# Peripherals.net
KiCad netlist of a schematic drawn in Altium Designer
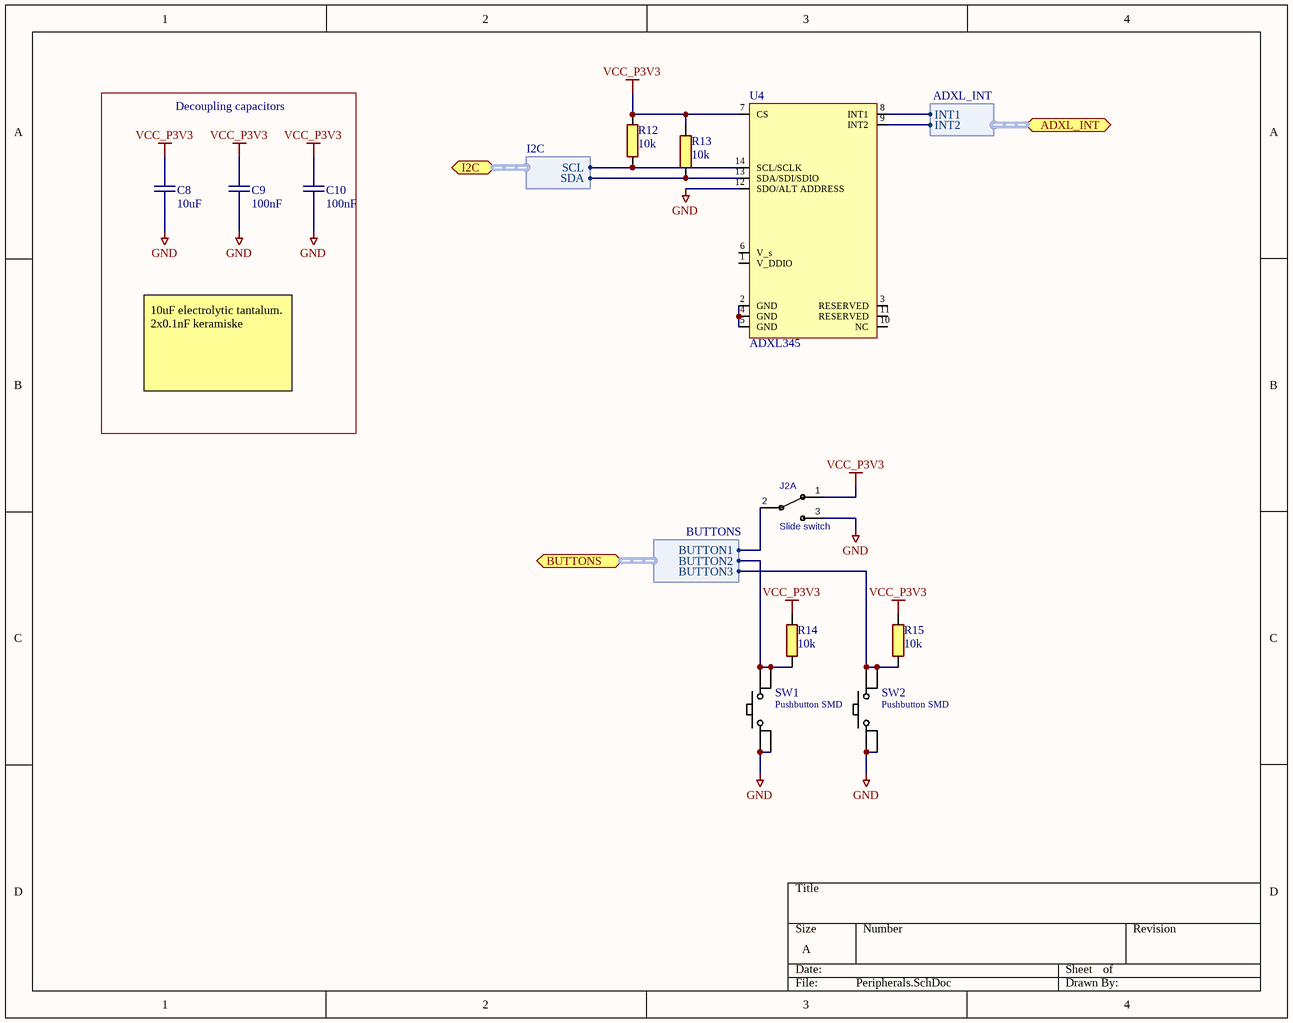
[diagram p0: Peripherals.SchDoc]

(export (version "E")
  (design (tool "Eeschema 10.0.6"))
  (components
    (comp (ref "C8")
      (value "10uF")
      (footprint "CAPC1206(3216)170_N")
      (description "X5R 50V 10%")
      (libsource (lib "OVLib") (part "CAP"))
    )
    (comp (ref "C9")
      (value "100nF")
      (footprint "CAPC0603(1608)55_N")
      (description "X7R 50V 5%")
      (libsource (lib "OVLib") (part "CAP"))
    )
    (comp (ref "C10")
      (value "100nF")
      (footprint "CAPC0603(1608)55_N")
      (description "X7R 50V 5%")
      (libsource (lib "OVLib") (part "CAP"))
    )
    (comp (ref "J2")
      (value "Slide switch")
      (footprint "OS202011MA0QS1")
      (description "Vinklet")
      (libsource (lib "OVLib") (part "Slide_switch_DPDT_RA"))
    )
    (comp (ref "R12")
      (value "10k")
      (footprint "RESC0603(1608)_N")
      (description "0.1W 1% Thick film resistor")
      (libsource (lib "OVLib") (part "Resistor2"))
    )
    (comp (ref "R13")
      (value "10k")
      (footprint "RESC0603(1608)_N")
      (description "0.1W 1% Thick film resistor")
      (libsource (lib "OVLib") (part "Resistor2"))
    )
    (comp (ref "R14")
      (value "10k")
      (footprint "RESC0603(1608)_N")
      (description "0.1W 1% Thick film resistor")
      (libsource (lib "OVLib") (part "Resistor2"))
    )
    (comp (ref "R15")
      (value "10k")
      (footprint "RESC0603(1608)_N")
      (description "0.1W 1% Thick film resistor")
      (libsource (lib "OVLib") (part "Resistor2"))
    )
    (comp (ref "SW1")
      (value "Pushbutton SMD")
      (footprint "SOIC254P500X160-4")
      (libsource (lib "OVLib") (part "Pushbutton"))
    )
    (comp (ref "SW2")
      (value "Pushbutton SMD")
      (footprint "SOIC254P500X160-4")
      (libsource (lib "OVLib") (part "Pushbutton"))
    )
    (comp (ref "U4") (value "ADXL345") (libsource (lib "Schlib1") (part "ADXL345")))
  )
  (nets
    (net (code "4") (name "/BUTTON1") (class "Default")
      (node (ref "J2") (pin "2") (pinfunction "2_2") (pintype "passive"))
    )
    (net (code "5") (name "/BUTTON2") (class "Default")
      (node (ref "R14") (pin "1") (pinfunction "1_1") (pintype "passive"))
      (node (ref "SW1") (pin "3") (pinfunction "3_3") (pintype "passive"))
      (node (ref "SW1") (pin "4") (pinfunction "4_4") (pintype "passive"))
    )
    (net (code "6") (name "/BUTTON3") (class "Default")
      (node (ref "R15") (pin "1") (pinfunction "1_1") (pintype "passive"))
      (node (ref "SW2") (pin "3") (pinfunction "3_3") (pintype "passive"))
      (node (ref "SW2") (pin "4") (pinfunction "4_4") (pintype "passive"))
    )
    (net (code "7") (name "/INT1") (class "Default")
      (node (ref "U4") (pin "8") (pinfunction "INT1_8") (pintype "passive"))
    )
    (net (code "8") (name "/INT2") (class "Default")
      (node (ref "U4") (pin "9") (pinfunction "INT2_9") (pintype "passive"))
    )
    (net (code "9") (name "/SCL") (class "Default")
      (node (ref "R12") (pin "1") (pinfunction "1_1") (pintype "passive"))
      (node (ref "U4") (pin "14") (pinfunction "SCL/SCLK_14") (pintype "passive"))
    )
    (net (code "10") (name "/SDA") (class "Default")
      (node (ref "R13") (pin "1") (pinfunction "1_1") (pintype "passive"))
      (node (ref "U4") (pin "13") (pinfunction "SDA/SDI/SDIO_13") (pintype "passive"))
    )
    (net (code "14") (name "GND") (class "Default")
      (node (ref "C10") (pin "1") (pinfunction "1_1") (pintype "passive"))
      (node (ref "C8") (pin "1") (pinfunction "1_1") (pintype "passive"))
      (node (ref "C9") (pin "1") (pinfunction "1_1") (pintype "passive"))
      (node (ref "J2") (pin "3") (pinfunction "3_3") (pintype "passive"))
      (node (ref "SW1") (pin "1") (pinfunction "1_1") (pintype "passive"))
      (node (ref "SW1") (pin "2") (pinfunction "2_2") (pintype "passive"))
      (node (ref "SW2") (pin "1") (pinfunction "1_1") (pintype "passive"))
      (node (ref "SW2") (pin "2") (pinfunction "2_2") (pintype "passive"))
      (node (ref "U4") (pin "12") (pinfunction "SDO/ALT_ADDRESS_12") (pintype "passive"))
    )
    (net (code "15") (name "Net-(U4-GND-Pad2)") (class "Default")
      (node (ref "U4") (pin "2") (pinfunction "GND_2") (pintype "passive"))
      (node (ref "U4") (pin "4") (pinfunction "GND_4") (pintype "passive"))
      (node (ref "U4") (pin "5") (pinfunction "GND_5") (pintype "passive"))
    )
    (net (code "16") (name "VCC_P3V3") (class "Default")
      (node (ref "C10") (pin "2") (pinfunction "2_2") (pintype "passive"))
      (node (ref "C8") (pin "2") (pinfunction "2_2") (pintype "passive"))
      (node (ref "C9") (pin "2") (pinfunction "2_2") (pintype "passive"))
      (node (ref "J2") (pin "1") (pinfunction "1_1") (pintype "passive"))
      (node (ref "R12") (pin "2") (pinfunction "2_2") (pintype "passive"))
      (node (ref "R13") (pin "2") (pinfunction "2_2") (pintype "passive"))
      (node (ref "R14") (pin "2") (pinfunction "2_2") (pintype "passive"))
      (node (ref "R15") (pin "2") (pinfunction "2_2") (pintype "passive"))
      (node (ref "U4") (pin "7") (pinfunction "CS_7") (pintype "passive"))
    )
    (net (code "17") (name "unconnected-(U4-NC-Pad10)") (class "Default")
      (node (ref "U4") (pin "10") (pinfunction "NC_10") (pintype "passive"))
    )
    (net (code "18") (name "unconnected-(U4-RESERVED-Pad3)") (class "Default")
      (node (ref "U4") (pin "3") (pinfunction "RESERVED_3") (pintype "passive"))
    )
    (net (code "19") (name "unconnected-(U4-RESERVED-Pad11)") (class "Default")
      (node (ref "U4") (pin "11") (pinfunction "RESERVED_11") (pintype "passive"))
    )
    (net (code "20") (name "unconnected-(U4-V_DDIO-Pad1)") (class "Default")
      (node (ref "U4") (pin "1") (pinfunction "V_DDIO_1") (pintype "passive"))
    )
    (net (code "21") (name "unconnected-(U4-V_s-Pad6)") (class "Default")
      (node (ref "U4") (pin "6") (pinfunction "V_s_6") (pintype "passive"))
    )
  )
)
